# TestingPCB.net
KiCad netlist of a schematic drawn in Altium Designer
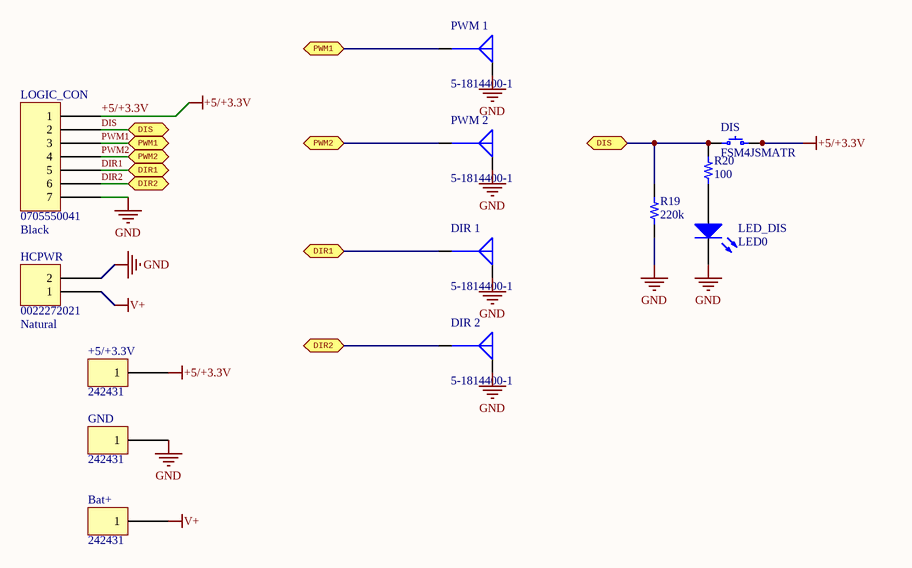
[diagram p0: TestingPCB.SchDoc]

(export (version "E")
  (design (tool "Eeschema 10.0.6"))
  (components
    (comp (ref "+5/+3.3V")
      (value "242431")
      (footprint "242431 Banana")
      (description "Banana PCB Connector")
      (fields (field (name "MANUFACTURER") "Multicomp") (field (name "VOLTAGE") "30V"))
      (libsource (lib "Celestial Library Database") (part "1 Pin"))
    )
    (comp (ref "Bat+")
      (value "242431")
      (footprint "242431 Banana")
      (description "Banana PCB Connector")
      (fields (field (name "MANUFACTURER") "Multicomp") (field (name "VOLTAGE") "30V"))
      (libsource (lib "Celestial Library Database") (part "1 Pin"))
    )
    (comp (ref "DIR 1")
      (value "5-1814400-1")
      (footprint "MOLEX SD-73100-0114")
      (description "CONN SMA JACK R/A 50 OHM PCB")
      (fields (field (name "MANUFACTURER") "TE Connectivity AMP Connectors"))
      (libsource (lib "Celestial Library Database") (part "RF Connector - SMA"))
    )
    (comp (ref "DIR 2")
      (value "5-1814400-1")
      (footprint "MOLEX SD-73100-0114")
      (description "CONN SMA JACK R/A 50 OHM PCB")
      (fields (field (name "MANUFACTURER") "TE Connectivity AMP Connectors"))
      (libsource (lib "Celestial Library Database") (part "RF Connector - SMA"))
    )
    (comp (ref "DIS")
      (value "FSM4JSMATR")
      (footprint "TE FSM4JSMA")
      (description "SWITCH TACTILE SPST-NO 0.05A 24V")
      (fields (field (name "MANUFACTURER") "TE Connectivity Alcoswitch Switches"))
      (libsource (lib "Celestial Library Database") (part "SPST-NO 4 PIN"))
    )
    (comp (ref "GND")
      (value "242431")
      (footprint "242431 Banana")
      (description "Banana PCB Connector")
      (fields (field (name "MANUFACTURER") "Multicomp") (field (name "VOLTAGE") "30V"))
      (libsource (lib "Celestial Library Database") (part "1 Pin"))
    )
    (comp (ref "HCPWR")
      (value "0022272021")
      (footprint "MOLEX KK 0022272021")
      (description "CONN HEADER 2POS .100 VERT TIN")
      (fields (field (name "COLOUR") "Natural") (field (name "MANUFACTURER") "Molex, LLC"))
      (libsource (lib "Celestial Library Database") (part "2 Pin"))
    )
    (comp (ref "LED_DIS")
      (value "LED0")
      (footprint "LED-0")
      (description "Typical INFRARED GaAs LED")
      (fields (field (name "PUBLISHER") "Altium Limited"))
      (libsource (lib "Miscellaneous Devices") (part "LED0"))
    )
    (comp (ref "LOGIC_CON")
      (value "0705550041")
      (footprint "MOLEX SDA-70555-7PIN")
      (description "CONN HEADER 7POS .100 R/A 15AU")
      (fields (field (name "COLOUR") "Black") (field (name "MANUFACTURER") "Molex, LLC"))
      (libsource (lib "Celestial Library Database") (part "7 Pin"))
    )
    (comp (ref "PWM 1")
      (value "5-1814400-1")
      (footprint "MOLEX SD-73100-0114")
      (description "CONN SMA JACK R/A 50 OHM PCB")
      (fields (field (name "MANUFACTURER") "TE Connectivity AMP Connectors"))
      (libsource (lib "Celestial Library Database") (part "RF Connector - SMA"))
    )
    (comp (ref "PWM 2")
      (value "5-1814400-1")
      (footprint "MOLEX SD-73100-0114")
      (description "CONN SMA JACK R/A 50 OHM PCB")
      (fields (field (name "MANUFACTURER") "TE Connectivity AMP Connectors"))
      (libsource (lib "Celestial Library Database") (part "RF Connector - SMA"))
    )
    (comp (ref "R19")
      (value "220k")
      (footprint "RES 0603/1608")
      (description "RES SMD 220K OHM 5% 1/4W 0603")
      (fields
        (field (name "PART NUMBER") "ERJ-PA3J224V")
        (field (name "MANUFACTURER") "Panasonic Electronic Components")
      )
      (libsource (lib "Celestial Library Database") (part "Resistor"))
    )
    (comp (ref "R20")
      (value "100")
      (footprint "RES 1206/3216")
      (description "RES SMD 100 OHM 0.1% 1/4W 1206")
      (fields
        (field (name "PART NUMBER") "ERA-8AEB101V")
        (field (name "MANUFACTURER") "Panasonic Electronic Components")
      )
      (libsource (lib "Celestial Library Database") (part "Resistor"))
    )
  )
  (nets
    (net (code "1") (name "+5{slash}+3.3V") (class "Default")
      (node (ref "+5/+3.3V") (pin "1") (pinfunction "1_1") (pintype "passive"))
      (node (ref "DIS") (pin "3") (pinfunction "3_3") (pintype "passive"))
      (node (ref "DIS") (pin "4") (pinfunction "4_4") (pintype "passive"))
      (node (ref "LOGIC_CON") (pin "1") (pinfunction "1_1") (pintype "passive"))
    )
    (net (code "2") (name "/DIR1") (class "Default")
      (node (ref "DIR 1") (pin "S") (pinfunction "S_S") (pintype "passive"))
      (node (ref "LOGIC_CON") (pin "5") (pinfunction "5_5") (pintype "passive"))
    )
    (net (code "3") (name "/DIR2") (class "Default")
      (node (ref "DIR 2") (pin "S") (pinfunction "S_S") (pintype "passive"))
      (node (ref "LOGIC_CON") (pin "6") (pinfunction "6_6") (pintype "passive"))
    )
    (net (code "4") (name "/DIS") (class "Default")
      (node (ref "DIS") (pin "1") (pinfunction "1_1") (pintype "passive"))
      (node (ref "DIS") (pin "2") (pinfunction "2_2") (pintype "passive"))
      (node (ref "LOGIC_CON") (pin "2") (pinfunction "2_2") (pintype "passive"))
      (node (ref "R19") (pin "2") (pinfunction "2_2") (pintype "passive"))
      (node (ref "R20") (pin "2") (pinfunction "2_2") (pintype "passive"))
    )
    (net (code "5") (name "/PWM1") (class "Default")
      (node (ref "LOGIC_CON") (pin "3") (pinfunction "3_3") (pintype "passive"))
      (node (ref "PWM 1") (pin "S") (pinfunction "S_S") (pintype "passive"))
    )
    (net (code "6") (name "/PWM2") (class "Default")
      (node (ref "LOGIC_CON") (pin "4") (pinfunction "4_4") (pintype "passive"))
      (node (ref "PWM 2") (pin "S") (pinfunction "S_S") (pintype "passive"))
    )
    (net (code "7") (name "GND") (class "Default")
      (node (ref "DIR 1") (pin "G") (pinfunction "G_G") (pintype "passive"))
      (node (ref "DIR 2") (pin "G") (pinfunction "G_G") (pintype "passive"))
      (node (ref "GND") (pin "1") (pinfunction "1_1") (pintype "passive"))
      (node (ref "HCPWR") (pin "2") (pinfunction "2_2") (pintype "passive"))
      (node (ref "LED_DIS") (pin "2") (pinfunction "K_2") (pintype "passive"))
      (node (ref "LOGIC_CON") (pin "7") (pinfunction "7_7") (pintype "passive"))
      (node (ref "PWM 1") (pin "G") (pinfunction "G_G") (pintype "passive"))
      (node (ref "PWM 2") (pin "G") (pinfunction "G_G") (pintype "passive"))
      (node (ref "R19") (pin "1") (pinfunction "1_1") (pintype "passive"))
    )
    (net (code "8") (name "Net-(LED_DIS-A)") (class "Default")
      (node (ref "LED_DIS") (pin "1") (pinfunction "A_1") (pintype "passive"))
      (node (ref "R20") (pin "1") (pinfunction "1_1") (pintype "passive"))
    )
    (net (code "9") (name "V+") (class "Default")
      (node (ref "Bat+") (pin "1") (pinfunction "1_1") (pintype "passive"))
      (node (ref "HCPWR") (pin "1") (pinfunction "1_1") (pintype "passive"))
    )
  )
)
